# PWM_controller_circuit.net
KiCad netlist of a schematic drawn in EAGLE
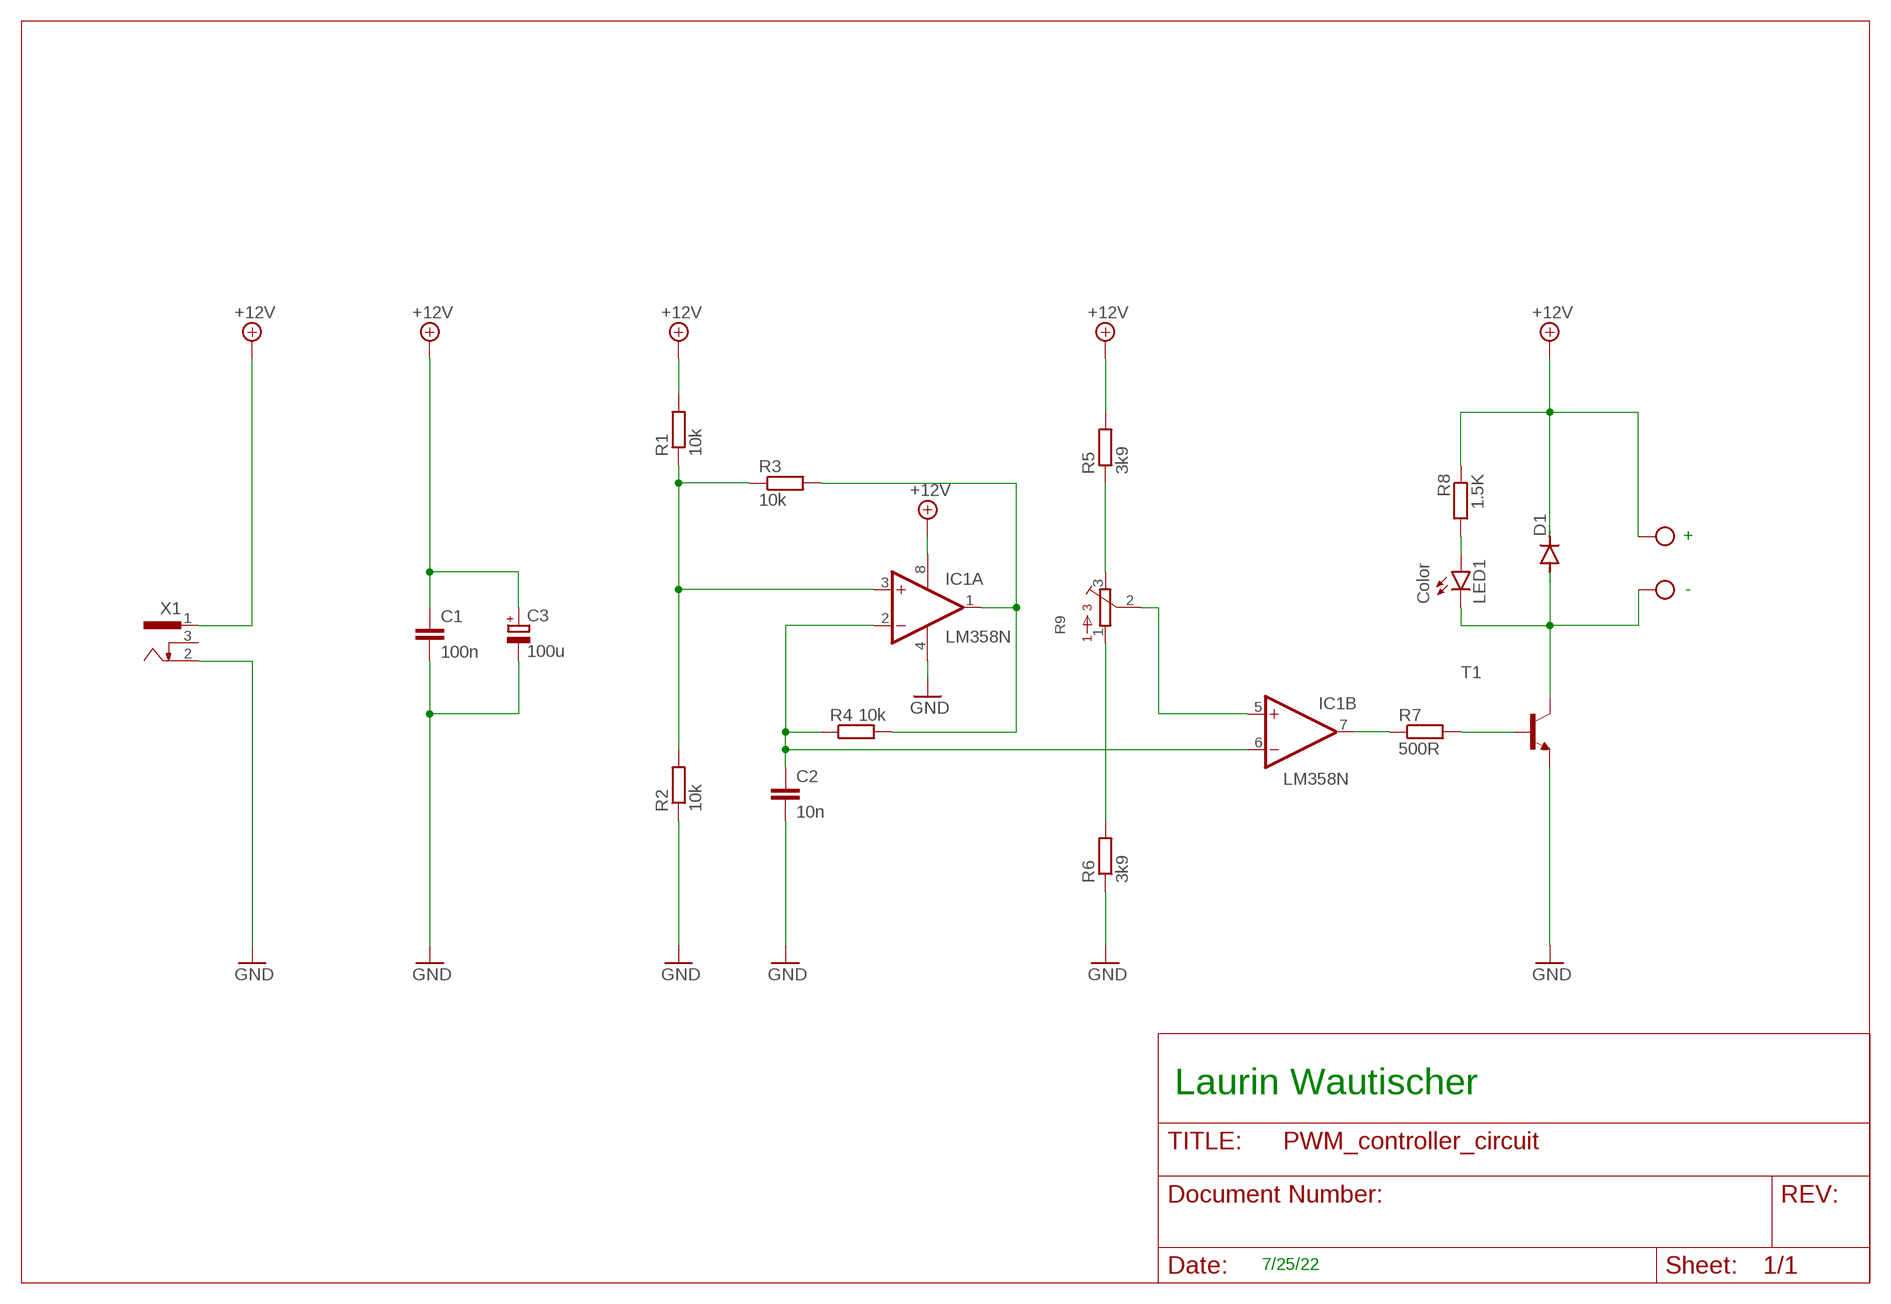
[diagram p0: schematic, sheet 1]

(export (version "E")
  (design (tool "Eeschema 10.0.6"))
  (components
    (comp (ref "C1")
      (value "100n")
      (footprint "eagle-import:C050-030X075")
      (libsource (lib "eagle-import") (part "C-EU050-030X075"))
    )
    (comp (ref "C2")
      (value "10n")
      (footprint "eagle-import:C050-030X075")
      (libsource (lib "eagle-import") (part "C-EU050-030X075"))
    )
    (comp (ref "C3")
      (value "100u")
      (footprint "eagle-import:E5-6")
      (libsource (lib "eagle-import") (part "CPOL-EUE5-6"))
    )
    (comp (ref "D1")
      (value "1N4004")
      (footprint "eagle-import:DO41-10")
      (libsource (lib "eagle-import") (part "1N4004"))
    )
    (comp (ref "IC1")
      (value "LM358N")
      (footprint "eagle-import:DIL08")
      (libsource (lib "eagle-import") (part "LM358N"))
    )
    (comp (ref "LED1")
      (value "Color")
      (footprint "eagle-import:LED3MM")
      (libsource (lib "eagle-import") (part "LED3MM"))
    )
    (comp (ref "R1")
      (value "10k")
      (footprint "eagle-import:0207_10")
      (libsource (lib "eagle-import") (part "R-EU_0207/10"))
    )
    (comp (ref "R2")
      (value "10k")
      (footprint "eagle-import:0207_10")
      (libsource (lib "eagle-import") (part "R-EU_0207/10"))
    )
    (comp (ref "R3")
      (value "10k")
      (footprint "eagle-import:0207_10")
      (libsource (lib "eagle-import") (part "R-EU_0207/10"))
    )
    (comp (ref "R4")
      (value "10k")
      (footprint "eagle-import:0207_10")
      (libsource (lib "eagle-import") (part "R-EU_0207/10"))
    )
    (comp (ref "R5")
      (value "3k9")
      (footprint "eagle-import:0207_10")
      (libsource (lib "eagle-import") (part "R-EU_0207/10"))
    )
    (comp (ref "R6")
      (value "3k9")
      (footprint "eagle-import:0207_10")
      (libsource (lib "eagle-import") (part "R-EU_0207/10"))
    )
    (comp (ref "R7")
      (value "500R")
      (footprint "eagle-import:0207_10")
      (libsource (lib "eagle-import") (part "R-EU_0207/10"))
    )
    (comp (ref "R8")
      (value "1.5K")
      (footprint "eagle-import:0207_10")
      (libsource (lib "eagle-import") (part "R-EU_0207/10"))
    )
    (comp (ref "R9")
      (value "3386-F")
      (footprint "eagle-import:3386F")
      (libsource (lib "eagle-import") (part "3386-F"))
    )
    (comp (ref "T1")
      (value "BC639-NPN-TO92-ECB")
      (footprint "eagle-import:TO92-ECB")
      (libsource (lib "eagle-import") (part "-NPN-TO92-ECBBC639"))
    )
    (comp (ref "X1")
      (value "733980-62")
      (footprint "eagle-import:733980-62")
      (libsource (lib "eagle-import") (part "73398?0-62"))
    )
    (comp (ref "X2")
      (value "MKDSN1,5/2-5,08")
      (footprint "eagle-import:MKDSN1,5_2-5,08")
      (libsource (lib "eagle-import") (part "MKDSN1,5/2-5,08"))
    )
  )
  (nets
    (net (code "1") (name "+12V") (class "Default")
      (node (ref "C1") (pin "1") (pinfunction "1_1") (pintype "passive"))
      (node (ref "C3") (pin "+") (pinfunction "+_+") (pintype "passive"))
      (node (ref "D1") (pin "C") (pinfunction "C_C") (pintype "passive"))
      (node (ref "IC1") (pin "8") (pinfunction "V+_8") (pintype "power_in"))
      (node (ref "R1") (pin "2") (pinfunction "2_2") (pintype "passive"))
      (node (ref "R5") (pin "2") (pinfunction "2_2") (pintype "passive"))
      (node (ref "R8") (pin "1") (pinfunction "1_1") (pintype "passive"))
      (node (ref "X1") (pin "1") (pinfunction "1_1") (pintype "passive"))
      (node (ref "X2") (pin "2") (pinfunction "KL_2") (pintype "passive"))
    )
    (net (code "2") (name "GND") (class "Default")
      (node (ref "C1") (pin "2") (pinfunction "2_2") (pintype "passive"))
      (node (ref "C2") (pin "2") (pinfunction "2_2") (pintype "passive"))
      (node (ref "C3") (pin "-") (pinfunction "-_-") (pintype "passive"))
      (node (ref "IC1") (pin "4") (pinfunction "V-_4") (pintype "power_in"))
      (node (ref "R2") (pin "1") (pinfunction "1_1") (pintype "passive"))
      (node (ref "R6") (pin "1") (pinfunction "1_1") (pintype "passive"))
      (node (ref "T1") (pin "E") (pinfunction "E_E") (pintype "passive"))
      (node (ref "X1") (pin "2") (pinfunction "2_2") (pintype "passive"))
    )
    (net (code "3") (name "Net-(IC1A-+IN)") (class "Default")
      (node (ref "IC1") (pin "3") (pinfunction "+IN_3") (pintype "input"))
      (node (ref "R1") (pin "1") (pinfunction "1_1") (pintype "passive"))
      (node (ref "R2") (pin "2") (pinfunction "2_2") (pintype "passive"))
      (node (ref "R3") (pin "1") (pinfunction "1_1") (pintype "passive"))
    )
    (net (code "4") (name "Net-(IC1A--IN)") (class "Default")
      (node (ref "C2") (pin "1") (pinfunction "1_1") (pintype "passive"))
      (node (ref "IC1") (pin "2") (pinfunction "-IN_2") (pintype "input"))
      (node (ref "IC1") (pin "6") (pinfunction "-IN_6") (pintype "input"))
      (node (ref "R4") (pin "1") (pinfunction "1_1") (pintype "passive"))
    )
    (net (code "5") (name "Net-(IC1A-OUT)") (class "Default")
      (node (ref "IC1") (pin "1") (pinfunction "OUT_1") (pintype "output"))
      (node (ref "R3") (pin "2") (pinfunction "2_2") (pintype "passive"))
      (node (ref "R4") (pin "2") (pinfunction "2_2") (pintype "passive"))
    )
    (net (code "6") (name "Net-(IC1B-+IN)") (class "Default")
      (node (ref "IC1") (pin "5") (pinfunction "+IN_5") (pintype "input"))
      (node (ref "R9") (pin "2") (pinfunction "2_2") (pintype "passive"))
    )
    (net (code "7") (name "Net-(IC1B-OUT)") (class "Default")
      (node (ref "IC1") (pin "7") (pinfunction "OUT_7") (pintype "output"))
      (node (ref "R7") (pin "1") (pinfunction "1_1") (pintype "passive"))
    )
    (net (code "8") (name "Net-(LED1-C)") (class "Default")
      (node (ref "D1") (pin "A") (pinfunction "A_A") (pintype "passive"))
      (node (ref "LED1") (pin "K") (pinfunction "C_K") (pintype "passive"))
      (node (ref "T1") (pin "C") (pinfunction "C_C") (pintype "passive"))
      (node (ref "X2") (pin "1") (pinfunction "KL_1") (pintype "passive"))
    )
    (net (code "9") (name "Net-(LED1-PadA)") (class "Default")
      (node (ref "LED1") (pin "A") (pinfunction "A_A") (pintype "passive"))
      (node (ref "R8") (pin "2") (pinfunction "2_2") (pintype "passive"))
    )
    (net (code "10") (name "Net-(R5-Pad1)") (class "Default")
      (node (ref "R5") (pin "1") (pinfunction "1_1") (pintype "passive"))
      (node (ref "R9") (pin "3") (pinfunction "3_3") (pintype "passive"))
    )
    (net (code "11") (name "Net-(R6-Pad2)") (class "Default")
      (node (ref "R6") (pin "2") (pinfunction "2_2") (pintype "passive"))
      (node (ref "R9") (pin "1") (pinfunction "1_1") (pintype "passive"))
    )
    (net (code "12") (name "Net-(R7-Pad2)") (class "Default")
      (node (ref "R7") (pin "2") (pinfunction "2_2") (pintype "passive"))
      (node (ref "T1") (pin "B") (pinfunction "B_B") (pintype "passive"))
    )
    (net (code "13") (name "unconnected-(X1-Pad3)") (class "Default")
      (node (ref "X1") (pin "3") (pinfunction "3_3") (pintype "passive"))
    )
  )
)
